# BoostConverter.net
KiCad netlist of a schematic drawn in Altium Designer
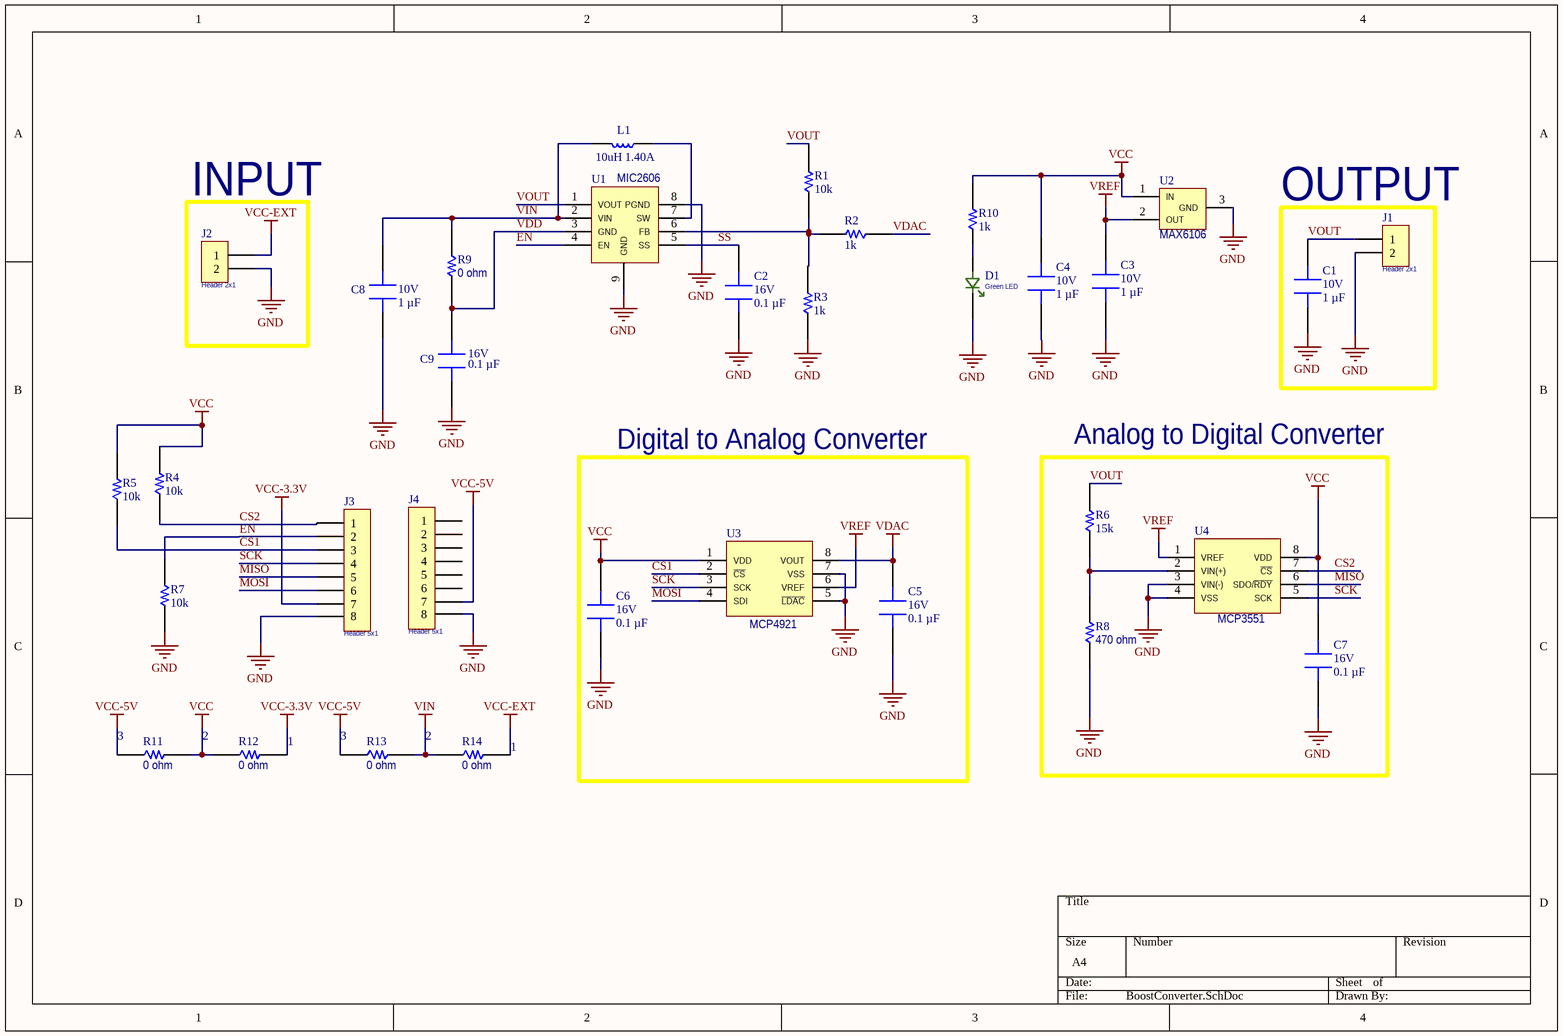
[diagram p0: BoostConverter.SchDoc]

(export (version "E")
  (design (tool "Eeschema 10.0.6"))
  (components
    (comp (ref "C1")
      (value "1 µF")
      (footprint "C0603-N")
      (description "CAP CER 1UF 10V X5R 0603")
      (fields
        (field (name "MANUFACTURER") "Samsung Electro-Mechanics")
        (field (name "DIGI-KEY PART NUMBER") "1276-1182-2-ND")
        (field (name "VOLTAGE") "10V")
      )
      (libsource (lib "BoostConverter") (part "CL10A105KP8NNNC"))
    )
    (comp (ref "C2")
      (value "0.1 µF")
      (footprint "C0603-N")
      (description "0.10µF ±5% 16V Ceramic Capacitor X7R 0603 (1608 Metric)")
      (fields
        (field (name "MANUFACTURER") "KYOCERA AVX")
        (field (name "DIGI-KEY PART NUMBER") "478-3726-2-ND")
        (field (name "VOLTAGE - RATED") "16V")
      )
      (libsource (lib "BoostConverter") (part "0603YC104JAT2A"))
    )
    (comp (ref "C3")
      (value "1 µF")
      (footprint "C0603-N")
      (description "CAP CER 1UF 10V X5R 0603")
      (fields
        (field (name "MANUFACTURER") "Samsung Electro-Mechanics")
        (field (name "DIGI-KEY PART NUMBER") "1276-1182-2-ND")
        (field (name "VOLTAGE") "10V")
      )
      (libsource (lib "BoostConverter") (part "CL10A105KP8NNNC"))
    )
    (comp (ref "C4")
      (value "1 µF")
      (footprint "C0603-N")
      (description "CAP CER 1UF 10V X5R 0603")
      (fields
        (field (name "MANUFACTURER") "Samsung Electro-Mechanics")
        (field (name "DIGI-KEY PART NUMBER") "1276-1182-2-ND")
        (field (name "VOLTAGE") "10V")
      )
      (libsource (lib "BoostConverter") (part "CL10A105KP8NNNC"))
    )
    (comp (ref "C5")
      (value "0.1 µF")
      (footprint "C0603-N")
      (description "0.10µF ±5% 16V Ceramic Capacitor X7R 0603 (1608 Metric)")
      (fields
        (field (name "MANUFACTURER") "KYOCERA AVX")
        (field (name "DIGI-KEY PART NUMBER") "478-3726-2-ND")
        (field (name "VOLTAGE") "16V")
      )
      (libsource (lib "BoostConverter") (part "0603YC104JAT2A"))
    )
    (comp (ref "C6")
      (value "0.1 µF")
      (footprint "C0603-N")
      (description "0.10µF ±5% 16V Ceramic Capacitor X7R 0603 (1608 Metric)")
      (fields
        (field (name "MANUFACTURER") "KYOCERA AVX")
        (field (name "DIGI-KEY PART NUMBER") "478-3726-2-ND")
        (field (name "VOLTAGE") "16V")
      )
      (libsource (lib "BoostConverter") (part "0603YC104JAT2A"))
    )
    (comp (ref "C7")
      (value "0.1 µF")
      (footprint "C0603-N")
      (description "0.10µF ±5% 16V Ceramic Capacitor X7R 0603 (1608 Metric)")
      (fields
        (field (name "MANUFACTURER") "KYOCERA AVX")
        (field (name "DIGI-KEY PART NUMBER") "478-3726-2-ND")
        (field (name "VOLTAGE") "16V")
      )
      (libsource (lib "BoostConverter") (part "0603YC104JAT2A"))
    )
    (comp (ref "C8")
      (value "1 µF")
      (footprint "C0603-N")
      (description "CAP CER 1UF 10V X5R 0603")
      (fields
        (field (name "MANUFACTURER") "Samsung Electro-Mechanics")
        (field (name "DIGI-KEY PART NUMBER") "1276-1182-2-ND")
        (field (name "VOLTAGE") "10V")
      )
      (libsource (lib "BoostConverter") (part "CL10A105KP8NNNC"))
    )
    (comp (ref "C9")
      (value "0.1 µF")
      (footprint "C0603-N")
      (description "0.10µF ±5% 16V Ceramic Capacitor X7R 0603 (1608 Metric)")
      (fields
        (field (name "MANUFACTURER") "KYOCERA AVX")
        (field (name "DIGI-KEY PART NUMBER") "478-3726-2-ND")
        (field (name "VOLTAGE") "16V")
      )
      (libsource (lib "BoostConverter") (part "0603YC104JAT2A"))
    )
    (comp (ref "D1")
      (value "Green LED")
      (footprint "QTLP601C4TR-0603")
      (description "Green 570nm LED Indication - Discrete 2.1V 0603 (1608 Metric)")
      (fields
        (field (name "MANUFACTURER") "Everlight Electronics Co Ltd")
        (field (name "DIGI-KEY PART NUMBER") "1080-1405-2-ND")
      )
      (libsource (lib "BoostConverter") (part "QTLP601C4TR"))
    )
    (comp (ref "J1")
      (value "ANCON02202P1757242")
      (footprint "796911-2")
      (description "TERM BLK 2P SIDE ENT 5.08MM PCB")
      (fields
        (field (name "MANUFACTURER") "Phoenix Contact")
        (field (name "DIGI-KEY PART NUMBER") "A121381-ND")
        (field (name "NAME") "Header 2x1")
      )
      (libsource (lib "BoostConverter") (part "796911-2"))
    )
    (comp (ref "J2")
      (value "ANCON02202P1757242")
      (footprint "796911-2")
      (description "TERM BLK 2P SIDE ENT 5.08MM PCB")
      (fields
        (field (name "MANUFACTURER") "Phoenix Contact")
        (field (name "DIGI-KEY PART NUMBER") "A121381-ND")
        (field (name "NAME") "Header 2x1")
      )
      (libsource (lib "") (part "796911-2_1"))
    )
    (comp (ref "J3")
      (value "Header 5x1")
      (footprint "8POS")
      (description "8 POS HEADER")
      (fields
        (field (name "MANUFACTURER") "Adam Tech")
        (field (name "DIGI-KEY PART NUMBER") "2057-PH1-08-UA-ND")
      )
      (libsource (lib "BoostConverter") (part "PH1-08-UA"))
    )
    (comp (ref "J4")
      (value "Header 5x1")
      (footprint "8POS")
      (description "8 POS HEADER")
      (fields
        (field (name "MANUFACTURER") "Adam Tech")
        (field (name "DIGI-KEY PART NUMBER") "2057-PH1-08-UA-ND")
      )
      (libsource (lib "") (part "PH1-08-UA_1"))
    )
    (comp (ref "L1")
      (value "10uH 1.40A")
      (footprint "SRU5028")
      (description "10uH, 1.40A, -40C +125C, SRU5028-100Y")
      (fields
        (field (name "MANUFACTURER") "Bourns Inc.")
        (field (name "DIGI-KEY PART NUMBER") "SRU5028-100YTR-ND")
      )
      (libsource (lib "BoostConverter") (part "SRU5028-100Y"))
    )
    (comp (ref "R1")
      (value "10k")
      (footprint "0603-N")
      (description "10K 1/10W 5% 0603")
      (fields (field (name "MANUFACTURER") "YAGEO") (field (name "DIGI-KEY PART NUMBER") "311-10.0KHRTR-ND"))
      (libsource (lib "BoostConverter") (part "RC0603FR-0710KL"))
    )
    (comp (ref "R2")
      (value "1k")
      (footprint "0603-N")
      (description "RES SMD 1K OHM 1% 1/3W 0603")
      (fields
        (field (name "MANUFACTURER") "Vishay Dale")
        (field (name "DIGI-KEY PART NUMBER") "541-1.00KSTR-ND")
      )
      (libsource (lib "BoostConverter") (part "CRCW06031K00FKEAHP"))
    )
    (comp (ref "R3")
      (value "1k")
      (footprint "0603-N")
      (description "RES SMD 1K OHM 1% 1/3W 0603")
      (fields
        (field (name "MANUFACTURER") "Vishay Dale")
        (field (name "DIGI-KEY PART NUMBER") "541-1.00KSTR-ND")
      )
      (libsource (lib "BoostConverter") (part "CRCW06031K00FKEAHP"))
    )
    (comp (ref "R4")
      (value "10k")
      (footprint "0603-N")
      (description "10K 1/10W 5% 0603")
      (fields
        (field (name "DIGI-KEY PART NUMBER") "311-10.0KHRTR-ND")
        (field (name "Comment") "ANRES10K006031T700")
      )
      (libsource (lib "BoostConverter") (part "RC0603FR-0710KL"))
    )
    (comp (ref "R5")
      (value "10k")
      (footprint "0603-N")
      (description "10K 1/10W 5% 0603")
      (fields (field (name "MANUFACTURER") "YAGEO") (field (name "DIGI-KEY PART NUMBER") "311-10.0KHRTR-ND"))
      (libsource (lib "BoostConverter") (part "RC0603FR-0710KL"))
    )
    (comp (ref "R6")
      (value "15k")
      (footprint "0805-N")
      (description "E24, 15K, 0805, %1")
      (fields
        (field (name "MANUFACTURER") "Panasonic - ECG")
        (field (name "DIGI-KEY PART NUMBER") "P15.0KCTR-ND")
      )
      (libsource (lib "BoostConverter") (part "ERJ-6ENF1502V"))
    )
    (comp (ref "R7")
      (value "10k")
      (footprint "0603-N")
      (description "10K 1/10W 5% 0603")
      (fields
        (field (name "DIGI-KEY PART NUMBER") "311-10.0KHRTR-ND")
        (field (name "Comment") "ANRES10K006031T700")
      )
      (libsource (lib "BoostConverter") (part "RC0603FR-0710KL"))
    )
    (comp (ref "R8")
      (value "470 ohm")
      (footprint "0603-N")
      (description "E24, 470R, 0603, %1")
      (fields
        (field (name "MANUFACTURER") "Panasonic Electronic Components")
        (field (name "DIGI-KEY PART NUMBER") "P470HTR-ND")
      )
      (libsource (lib "BoostConverter") (part "ERJ-3EKF4700V"))
    )
    (comp (ref "R9")
      (value "0 ohm")
      (footprint "0402-N")
      (description "0R, 0402, Thick Film, 1/16W, %1")
      (fields
        (field (name "MANUFACTURER") "TE Connectivity Passive Product")
        (field (name "DIGI-KEY PART NUMBER") "A106025TR-ND")
      )
      (libsource (lib "BoostConverter") (part "6-1622826-4"))
    )
    (comp (ref "R10")
      (value "1k")
      (footprint "0603-N")
      (description "RES SMD 1K OHM 1% 1/3W 0603")
      (fields
        (field (name "MANUFACTURER") "Vishay Dale")
        (field (name "DIGI-KEY PART NUMBER") "541-1.00KSTR-ND")
      )
      (libsource (lib "BoostConverter") (part "CRCW06031K00FKEAHP"))
    )
    (comp (ref "R11")
      (value "0 ohm")
      (footprint "0402-N")
      (description "0R, 0402, Thick Film, 1/16W, %1")
      (fields
        (field (name "MANUFACTURER") "TE Connectivity Passive Product")
        (field (name "DIGI-KEY PART NUMBER") "A106025TR-ND")
      )
      (libsource (lib "BoostConverter") (part "6-1622826-4"))
    )
    (comp (ref "R12")
      (value "0 ohm")
      (footprint "0402-N")
      (description "0R, 0402, Thick Film, 1/16W, %1")
      (fields
        (field (name "DIGI-KEY PART NUMBER") "A106025TR-ND")
        (field (name "MANUFECTURER PART NUMBER") "CRG0402ZR")
      )
      (libsource (lib "BoostConverter") (part "6-1622826-4"))
    )
    (comp (ref "R13")
      (value "0 ohm")
      (footprint "0402-N")
      (description "0R, 0402, Thick Film, 1/16W, %1")
      (fields
        (field (name "MANUFACTURER") "TE Connectivity Passive Product")
        (field (name "DIGI-KEY PART NUMBER") "A106025TR-ND")
      )
      (libsource (lib "BoostConverter") (part "6-1622826-4"))
    )
    (comp (ref "R14")
      (value "0 ohm")
      (footprint "0402-N")
      (description "0R, 0402, Thick Film, 1/16W, %1")
      (fields
        (field (name "MANUFACTURER") "TE Connectivity Passive Product")
        (field (name "DIGI-KEY PART NUMBER") "A106025TR-ND")
      )
      (libsource (lib "BoostConverter") (part "6-1622826-4"))
    )
    (comp (ref "U1")
      (value "ANICMIC2606YMLTR00")
      (footprint "MIC2606YML-TR")
      (description "IC REG BOOST ADJ 500MA 8MLF")
      (fields (field (name "MANUFACTURER") "Microchip Technology") (field (name "NAME") "MIC2606"))
      (libsource (lib "BoostConverter") (part "MIC2606YML-TR"))
    )
    (comp (ref "U2")
      (value "ANICMAX6106EURTTRN")
      (footprint "MAX6106EUR+T")
      (description "IC VREF SERIES 0.4% SOT23-3")
      (fields
        (field (name "MANUFACTURER") "Analog Devices Inc./Maxim Integrated")
        (field (name "NAME") "MAX6106")
      )
      (libsource (lib "BoostConverter") (part "MAX6106EUR+T"))
    )
    (comp (ref "U3")
      (value "ANICMCP4921EMCND00")
      (footprint "MCP4921T-E/SN")
      (description "IC DAC 12BIT V-OUT 8DFN")
      (fields
        (field (name "MANUFACTURER") "Microchip Technology")
        (field (name "DIGI-KEY PART NUMBER") "MCP4921T-E/SNTR-ND")
        (field (name "NAME") "MCP4921")
      )
      (libsource (lib "BoostConverter") (part "MCP4921T-E/SN"))
    )
    (comp (ref "U4")
      (value "ANICMCP3551ESNND00")
      (footprint "MCP3551-E/SN")
      (description "IC ADC 22BIT SIGMA-DELTA 8SOIC")
      (fields (field (name "MANUFACTURER") "Microchip Technology") (field (name "NAME") "MCP3551"))
      (libsource (lib "BoostConverter") (part "MCP3551-E/SN"))
    )
  )
  (nets
    (net (code "2") (name "/CS1") (class "Default")
      (node (ref "J3") (pin "3") (pinfunction "3_3") (pintype "passive"))
      (node (ref "R5") (pin "1") (pinfunction "1_1") (pintype "passive"))
      (node (ref "U3") (pin "2") (pinfunction "~{CS}_2") (pintype "passive"))
    )
    (net (code "3") (name "/CS2") (class "Default")
      (node (ref "J3") (pin "1") (pinfunction "1_1") (pintype "passive"))
      (node (ref "R4") (pin "1") (pinfunction "1_1") (pintype "passive"))
      (node (ref "U4") (pin "7") (pinfunction "~{CS}_7") (pintype "passive"))
    )
    (net (code "4") (name "/EN") (class "Default")
      (node (ref "J3") (pin "2") (pinfunction "2_2") (pintype "passive"))
      (node (ref "R7") (pin "1") (pinfunction "1_1") (pintype "passive"))
      (node (ref "U1") (pin "4") (pinfunction "EN_4") (pintype "passive"))
    )
    (net (code "5") (name "/MISO") (class "Default")
      (node (ref "J3") (pin "5") (pinfunction "5_5") (pintype "passive"))
      (node (ref "U4") (pin "6") (pinfunction "SDO/~{RDY}_6") (pintype "passive"))
    )
    (net (code "6") (name "/MOSI") (class "Default")
      (node (ref "J3") (pin "6") (pinfunction "6_6") (pintype "passive"))
      (node (ref "U3") (pin "4") (pinfunction "SDI_4") (pintype "passive"))
    )
    (net (code "7") (name "/SCK") (class "Default")
      (node (ref "J3") (pin "4") (pinfunction "4_4") (pintype "passive"))
      (node (ref "U3") (pin "3") (pinfunction "SCK_3") (pintype "passive"))
      (node (ref "U4") (pin "5") (pinfunction "SCK_5") (pintype "passive"))
    )
    (net (code "8") (name "/SS") (class "Default")
      (node (ref "C2") (pin "2") (pinfunction "2_2") (pintype "passive"))
      (node (ref "U1") (pin "5") (pinfunction "SS_5") (pintype "passive"))
    )
    (net (code "9") (name "/VDD") (class "Default")
      (node (ref "C9") (pin "1") (pinfunction "1_1") (pintype "passive"))
      (node (ref "R9") (pin "2") (pinfunction "2_2") (pintype "passive"))
      (node (ref "U1") (pin "3") (pinfunction "GND_3") (pintype "passive"))
    )
    (net (code "10") (name "/VOUT") (class "Default")
      (node (ref "C1") (pin "2") (pinfunction "2_2") (pintype "passive"))
      (node (ref "J1") (pin "1") (pinfunction "1_1") (pintype "passive"))
      (node (ref "R1") (pin "2") (pinfunction "2_2") (pintype "passive"))
      (node (ref "R6") (pin "2") (pinfunction "2_2") (pintype "passive"))
      (node (ref "U1") (pin "1") (pinfunction "VOUT_1") (pintype "passive"))
    )
    (net (code "11") (name "GND") (class "Default")
      (node (ref "C1") (pin "1") (pinfunction "1_1") (pintype "passive"))
      (node (ref "C2") (pin "1") (pinfunction "1_1") (pintype "passive"))
      (node (ref "C3") (pin "2") (pinfunction "2_2") (pintype "passive"))
      (node (ref "C4") (pin "2") (pinfunction "2_2") (pintype "passive"))
      (node (ref "C5") (pin "1") (pinfunction "1_1") (pintype "passive"))
      (node (ref "C6") (pin "1") (pinfunction "1_1") (pintype "passive"))
      (node (ref "C7") (pin "1") (pinfunction "1_1") (pintype "passive"))
      (node (ref "C8") (pin "2") (pinfunction "2_2") (pintype "passive"))
      (node (ref "C9") (pin "2") (pinfunction "2_2") (pintype "passive"))
      (node (ref "D1") (pin "2") (pinfunction "2_2") (pintype "passive"))
      (node (ref "J1") (pin "2") (pinfunction "2_2") (pintype "passive"))
      (node (ref "J2") (pin "2") (pinfunction "2_2") (pintype "passive"))
      (node (ref "J3") (pin "8") (pinfunction "8_8") (pintype "passive"))
      (node (ref "J4") (pin "8") (pinfunction "8_8") (pintype "passive"))
      (node (ref "R3") (pin "1") (pinfunction "1_1") (pintype "passive"))
      (node (ref "R7") (pin "2") (pinfunction "2_2") (pintype "passive"))
      (node (ref "R8") (pin "1") (pinfunction "1_1") (pintype "passive"))
      (node (ref "U1") (pin "8") (pinfunction "PGND_8") (pintype "passive"))
      (node (ref "U1") (pin "9") (pinfunction "GND_9") (pintype "passive"))
      (node (ref "U2") (pin "3") (pinfunction "GND_3") (pintype "passive"))
      (node (ref "U3") (pin "5") (pinfunction "~{LDAC}_5") (pintype "passive"))
      (node (ref "U3") (pin "7") (pinfunction "VSS_7") (pintype "passive"))
      (node (ref "U4") (pin "3") (pinfunction "VIN(-)_3") (pintype "passive"))
      (node (ref "U4") (pin "4") (pinfunction "VSS_4") (pintype "passive"))
    )
    (net (code "12") (name "Net-(D1-Pad1)") (class "Default")
      (node (ref "D1") (pin "1") (pinfunction "1_1") (pintype "passive"))
      (node (ref "R10") (pin "1") (pinfunction "1_1") (pintype "passive"))
    )
    (net (code "13") (name "Net-(U1-FB)") (class "Default")
      (node (ref "R1") (pin "1") (pinfunction "1_1") (pintype "passive"))
      (node (ref "R2") (pin "2") (pinfunction "2_2") (pintype "passive"))
      (node (ref "R3") (pin "2") (pinfunction "2_2") (pintype "passive"))
      (node (ref "U1") (pin "6") (pinfunction "FB_6") (pintype "passive"))
    )
    (net (code "14") (name "Net-(U1-SW)") (class "Default")
      (node (ref "L1") (pin "1") (pinfunction "1_1") (pintype "passive"))
      (node (ref "U1") (pin "7") (pinfunction "SW_7") (pintype "passive"))
    )
    (net (code "15") (name "Net-(U4-VIN(+))") (class "Default")
      (node (ref "R6") (pin "1") (pinfunction "1_1") (pintype "passive"))
      (node (ref "R8") (pin "2") (pinfunction "2_2") (pintype "passive"))
      (node (ref "U4") (pin "2") (pinfunction "VIN(+)_2") (pintype "passive"))
    )
    (net (code "16") (name "VCC") (class "Default")
      (node (ref "C4") (pin "1") (pinfunction "1_1") (pintype "passive"))
      (node (ref "C6") (pin "2") (pinfunction "2_2") (pintype "passive"))
      (node (ref "C7") (pin "2") (pinfunction "2_2") (pintype "passive"))
      (node (ref "R10") (pin "2") (pinfunction "2_2") (pintype "passive"))
      (node (ref "R11") (pin "2") (pinfunction "2_2") (pintype "passive"))
      (node (ref "R12") (pin "1") (pinfunction "1_1") (pintype "passive"))
      (node (ref "R4") (pin "2") (pinfunction "2_2") (pintype "passive"))
      (node (ref "R5") (pin "2") (pinfunction "2_2") (pintype "passive"))
      (node (ref "U2") (pin "1") (pinfunction "IN_1") (pintype "passive"))
      (node (ref "U3") (pin "1") (pinfunction "VDD_1") (pintype "passive"))
      (node (ref "U4") (pin "8") (pinfunction "VDD_8") (pintype "passive"))
    )
    (net (code "17") (name "VCC-3.3V") (class "Default")
      (node (ref "J3") (pin "7") (pinfunction "7_7") (pintype "passive"))
      (node (ref "R12") (pin "2") (pinfunction "2_2") (pintype "passive"))
    )
    (net (code "18") (name "VCC-5V") (class "Default")
      (node (ref "J4") (pin "7") (pinfunction "7_7") (pintype "passive"))
      (node (ref "R11") (pin "1") (pinfunction "1_1") (pintype "passive"))
      (node (ref "R13") (pin "1") (pinfunction "1_1") (pintype "passive"))
    )
    (net (code "19") (name "VCC-EXT") (class "Default")
      (node (ref "J2") (pin "1") (pinfunction "1_1") (pintype "passive"))
      (node (ref "R14") (pin "2") (pinfunction "2_2") (pintype "passive"))
    )
    (net (code "20") (name "VDAC") (class "Default")
      (node (ref "C5") (pin "2") (pinfunction "2_2") (pintype "passive"))
      (node (ref "R2") (pin "1") (pinfunction "1_1") (pintype "passive"))
      (node (ref "U3") (pin "8") (pinfunction "VOUT_8") (pintype "passive"))
    )
    (net (code "21") (name "VIN") (class "Default")
      (node (ref "C8") (pin "1") (pinfunction "1_1") (pintype "passive"))
      (node (ref "L1") (pin "2") (pinfunction "2_2") (pintype "passive"))
      (node (ref "R13") (pin "2") (pinfunction "2_2") (pintype "passive"))
      (node (ref "R14") (pin "1") (pinfunction "1_1") (pintype "passive"))
      (node (ref "R9") (pin "1") (pinfunction "1_1") (pintype "passive"))
      (node (ref "U1") (pin "2") (pinfunction "VIN_2") (pintype "passive"))
    )
    (net (code "22") (name "VREF") (class "Default")
      (node (ref "C3") (pin "1") (pinfunction "1_1") (pintype "passive"))
      (node (ref "U2") (pin "2") (pinfunction "OUT_2") (pintype "passive"))
      (node (ref "U3") (pin "6") (pinfunction "VREF_6") (pintype "passive"))
      (node (ref "U4") (pin "1") (pinfunction "VREF_1") (pintype "passive"))
    )
    (net (code "23") (name "unconnected-(J4-Pad1)") (class "Default")
      (node (ref "J4") (pin "1") (pinfunction "1_1") (pintype "passive"))
    )
    (net (code "24") (name "unconnected-(J4-Pad2)") (class "Default")
      (node (ref "J4") (pin "2") (pinfunction "2_2") (pintype "passive"))
    )
    (net (code "25") (name "unconnected-(J4-Pad3)") (class "Default")
      (node (ref "J4") (pin "3") (pinfunction "3_3") (pintype "passive"))
    )
    (net (code "26") (name "unconnected-(J4-Pad4)") (class "Default")
      (node (ref "J4") (pin "4") (pinfunction "4_4") (pintype "passive"))
    )
    (net (code "27") (name "unconnected-(J4-Pad5)") (class "Default")
      (node (ref "J4") (pin "5") (pinfunction "5_5") (pintype "passive"))
    )
    (net (code "28") (name "unconnected-(J4-Pad6)") (class "Default")
      (node (ref "J4") (pin "6") (pinfunction "6_6") (pintype "passive"))
    )
  )
)
